# ACME_V4.net
KiCad netlist of a schematic drawn in EAGLE
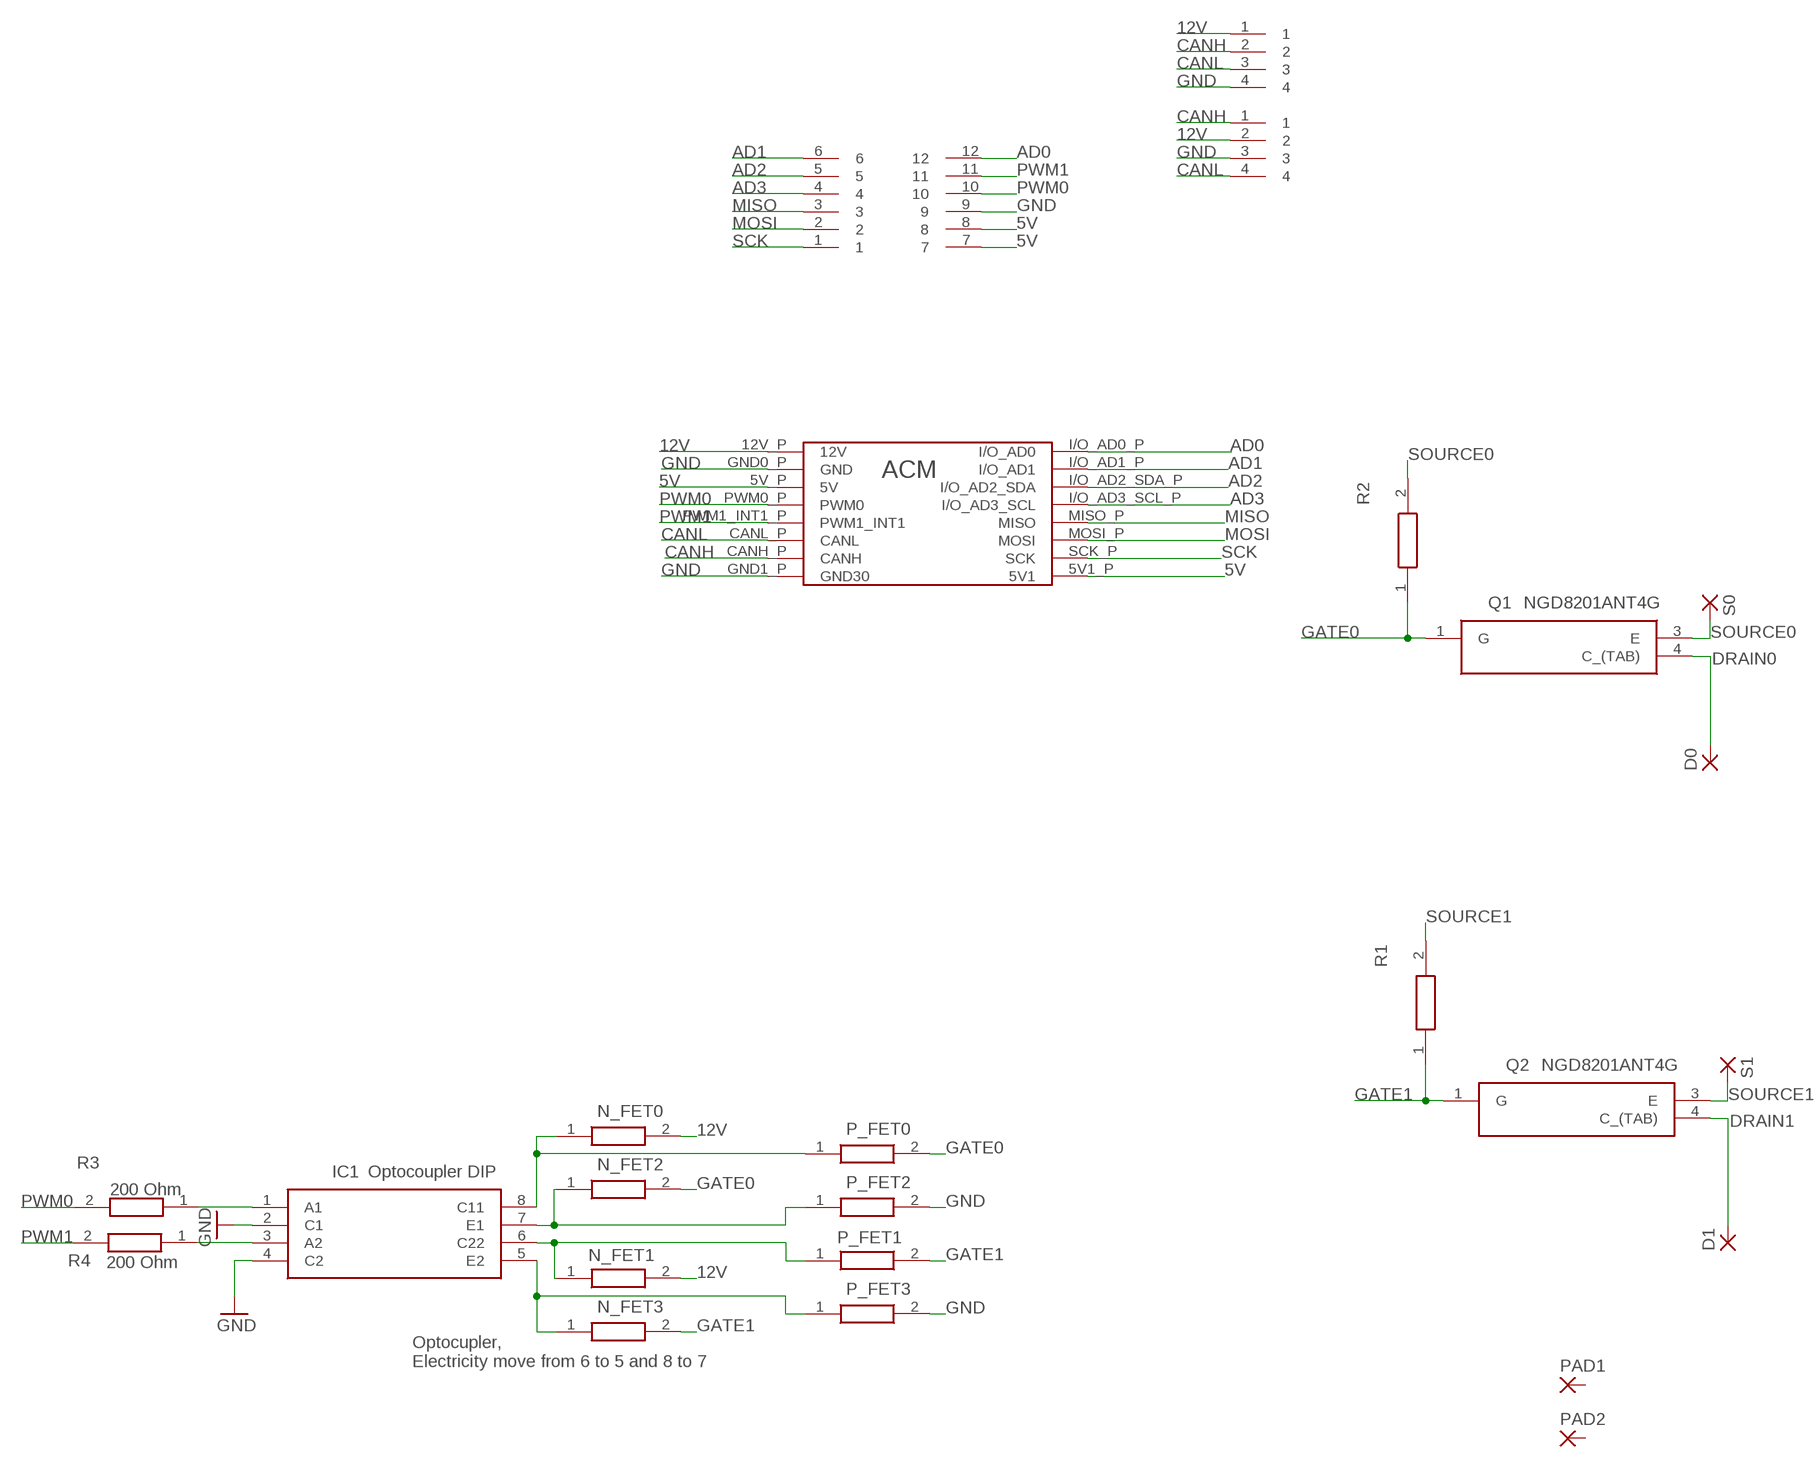
[diagram p0: schematic, sheet 1]

(export (version "E")
  (design (tool "Eeschema 10.0.6"))
  (components
    (comp (ref "D0")
      (value "WIREPADSMD5-2,5")
      (footprint "eagle-import:5-2,5")
      (libsource (lib "eagle-import") (part "WIREPADSMD5-2,5"))
    )
    (comp (ref "D1")
      (value "WIREPADSMD5-2,5")
      (footprint "eagle-import:5-2,5")
      (libsource (lib "eagle-import") (part "WIREPADSMD5-2,5"))
    )
    (comp (ref "IC1")
      (value "Optocoupler DIP")
      (footprint "eagle-import:DIP762W60P254L966H485Q8N")
      (fields
        (field (name "MANUFACTURER_PART_NUMBER") "TLP350(F)")
        (field (name "MOUSER_PART_NUMBER") "757-TLP350(F)")
        (field (name "RS_PART_NUMBER") "0186022P")
      )
      (libsource (lib "eagle-import") (part "TLP350(F)"))
    )
    (comp (ref "N_FET0")
      (value "ERA-3AEB2262V")
      (footprint "eagle-import:RESC1608X55N")
      (fields (field (name "MOUSER_PART_NUMBER") "667-ERA-3AEB2262V"))
      (libsource (lib "eagle-import") (part "ERA-3AEB2262V"))
    )
    (comp (ref "N_FET1")
      (value "ERA-3AEB2262V")
      (footprint "eagle-import:RESC1608X55N")
      (fields (field (name "MOUSER_PART_NUMBER") "667-ERA-3AEB2262V"))
      (libsource (lib "eagle-import") (part "ERA-3AEB2262V"))
    )
    (comp (ref "N_FET2")
      (value "ERA-3AEB2262V")
      (footprint "eagle-import:RESC1608X55N")
      (fields (field (name "MOUSER_PART_NUMBER") "667-ERA-3AEB2262V"))
      (libsource (lib "eagle-import") (part "ERA-3AEB2262V"))
    )
    (comp (ref "N_FET3")
      (value "ERA-3AEB2262V")
      (footprint "eagle-import:RESC1608X55N")
      (fields (field (name "MOUSER_PART_NUMBER") "667-ERA-3AEB2262V"))
      (libsource (lib "eagle-import") (part "ERA-3AEB2262V"))
    )
    (comp (ref "PAD1")
      (value "2,54/1,1")
      (footprint "eagle-import:2,54_1,1")
      (libsource (lib "eagle-import") (part "2,54/1,1"))
    )
    (comp (ref "PAD2")
      (value "2,54/1,1")
      (footprint "eagle-import:2,54_1,1")
      (libsource (lib "eagle-import") (part "2,54/1,1"))
    )
    (comp (ref "P_FET0")
      (value "ERA-3AEB2262V")
      (footprint "eagle-import:RESC1608X55N")
      (fields (field (name "MOUSER_PART_NUMBER") "667-ERA-3AEB2262V"))
      (libsource (lib "eagle-import") (part "ERA-3AEB2262V"))
    )
    (comp (ref "P_FET1")
      (value "ERA-3AEB2262V")
      (footprint "eagle-import:RESC1608X55N")
      (fields (field (name "MOUSER_PART_NUMBER") "667-ERA-3AEB2262V"))
      (libsource (lib "eagle-import") (part "ERA-3AEB2262V"))
    )
    (comp (ref "P_FET2")
      (value "ERA-3AEB2262V")
      (footprint "eagle-import:RESC1608X55N")
      (fields (field (name "MOUSER_PART_NUMBER") "667-ERA-3AEB2262V"))
      (libsource (lib "eagle-import") (part "ERA-3AEB2262V"))
    )
    (comp (ref "P_FET3")
      (value "ERA-3AEB2262V")
      (footprint "eagle-import:RESC1608X55N")
      (fields (field (name "MOUSER_PART_NUMBER") "667-ERA-3AEB2262V"))
      (libsource (lib "eagle-import") (part "ERA-3AEB2262V"))
    )
    (comp (ref "Q1")
      (value "NGD8201ANT4G")
      (footprint "eagle-import:TO229P990X238-4N")
      (fields (field (name "MOUSER_PART_NUMBER") "7470901"))
      (libsource (lib "eagle-import") (part "NGD8201ANT4G"))
    )
    (comp (ref "Q2")
      (value "NGD8201ANT4G")
      (footprint "eagle-import:TO229P990X238-4N")
      (fields (field (name "MOUSER_PART_NUMBER") "7470901"))
      (libsource (lib "eagle-import") (part "NGD8201ANT4G"))
    )
    (comp (ref "R1")
      (value "ERA-3AEB2262V")
      (footprint "eagle-import:RESC1608X55N")
      (fields (field (name "MOUSER_PART_NUMBER") "667-ERA-3AEB2262V"))
      (libsource (lib "eagle-import") (part "ERA-3AEB2262V"))
    )
    (comp (ref "R2")
      (value "ERA-3AEB2262V")
      (footprint "eagle-import:RESC1608X55N")
      (fields (field (name "MOUSER_PART_NUMBER") "667-ERA-3AEB2262V"))
      (libsource (lib "eagle-import") (part "ERA-3AEB2262V"))
    )
    (comp (ref "R3")
      (value "200 Ohm")
      (footprint "eagle-import:RESC1608X55N")
      (fields
        (field (name "MANUFACTURER_PART_NUMBER") "ERA-3AEB2262V")
        (field (name "MOUSER_PART_NUMBER") "667-ERA-3AEB2262V")
      )
      (libsource (lib "eagle-import") (part "ERA-3AEB2262V"))
    )
    (comp (ref "R4")
      (value "200 Ohm")
      (footprint "eagle-import:RESC1608X55N")
      (fields
        (field (name "MANUFACTURER_PART_NUMBER") "ERA-3AEB2262V")
        (field (name "MOUSER_PART_NUMBER") "667-ERA-3AEB2262V")
      )
      (libsource (lib "eagle-import") (part "ERA-3AEB2262V"))
    )
    (comp (ref "S0")
      (value "WIREPADSMD5-2,5")
      (footprint "eagle-import:5-2,5")
      (libsource (lib "eagle-import") (part "WIREPADSMD5-2,5"))
    )
    (comp (ref "S1")
      (value "WIREPADSMD5-2,5")
      (footprint "eagle-import:5-2,5")
      (libsource (lib "eagle-import") (part "WIREPADSMD5-2,5"))
    )
    (comp (ref "U$1")
      (value "ACM_CASTELLATED")
      (footprint "eagle-import:ACM_CAS_FP")
      (libsource (lib "eagle-import") (part "ACM_CASTELLATED"))
    )
    (comp (ref "U$2")
      (value "16P_CONNECTOR")
      (footprint "eagle-import:16P_CONNECTOR_FP")
      (libsource (lib "eagle-import") (part "16P_CONNECTOR"))
    )
    (comp (ref "U$3")
      (value "16P_CONNECTOR")
      (footprint "eagle-import:16P_CONNECTOR_FP")
      (libsource (lib "eagle-import") (part "4P_Connector holes_16P_CONNECTOR"))
    )
    (comp (ref "U$4")
      (value "16P_CONNECTOR")
      (footprint "eagle-import:16P_CONNECTOR_FP")
      (libsource (lib "eagle-import") (part "4P_Connector holes_16P_CONNECTOR"))
    )
  )
  (nets
    (net (code "1") (name "/5V") (class "Default")
      (node (ref "U$1") (pin "5V1_P") (pinfunction "5V1_5V1_P") (pintype "bidirectional"))
      (node (ref "U$1") (pin "5V_P") (pinfunction "5V_5V_P") (pintype "bidirectional"))
      (node (ref "U$2") (pin "7") (pinfunction "7_7") (pintype "bidirectional"))
      (node (ref "U$2") (pin "8") (pinfunction "8_8") (pintype "bidirectional"))
    )
    (net (code "2") (name "/12V") (class "Default")
      (node (ref "N_FET0") (pin "2") (pinfunction "2_2") (pintype "bidirectional"))
      (node (ref "N_FET1") (pin "2") (pinfunction "2_2") (pintype "bidirectional"))
      (node (ref "U$1") (pin "12V_P") (pinfunction "12V_12V_P") (pintype "bidirectional"))
      (node (ref "U$3") (pin "1") (pinfunction "1_1") (pintype "bidirectional"))
      (node (ref "U$4") (pin "2") (pinfunction "2_2") (pintype "bidirectional"))
    )
    (net (code "3") (name "/AD0") (class "Default")
      (node (ref "U$1") (pin "I/O_AD0_P") (pinfunction "I/O_AD0_I/O_AD0_P") (pintype "bidirectional"))
      (node (ref "U$2") (pin "12") (pinfunction "12_12") (pintype "bidirectional"))
    )
    (net (code "4") (name "/AD1") (class "Default")
      (node (ref "U$1") (pin "I/O_AD1_P") (pinfunction "I/O_AD1_I/O_AD1_P") (pintype "bidirectional"))
      (node (ref "U$2") (pin "6") (pinfunction "6_6") (pintype "bidirectional"))
    )
    (net (code "5") (name "/AD2") (class "Default")
      (node (ref "U$1") (pin "I/O_AD2_SDA_P") (pinfunction "I/O_AD2_SDA_I/O_AD2_SDA_P") (pintype "bidirectional"))
      (node (ref "U$2") (pin "5") (pinfunction "5_5") (pintype "bidirectional"))
    )
    (net (code "6") (name "/AD3") (class "Default")
      (node (ref "U$1") (pin "I/O_AD3_SCL_P") (pinfunction "I/O_AD3_SCL_I/O_AD3_SCL_P") (pintype "bidirectional"))
      (node (ref "U$2") (pin "4") (pinfunction "4_4") (pintype "bidirectional"))
    )
    (net (code "7") (name "/CANH") (class "Default")
      (node (ref "U$1") (pin "CANH_P") (pinfunction "CANH_CANH_P") (pintype "bidirectional"))
      (node (ref "U$3") (pin "2") (pinfunction "2_2") (pintype "bidirectional"))
      (node (ref "U$4") (pin "1") (pinfunction "1_1") (pintype "bidirectional"))
    )
    (net (code "8") (name "/CANL") (class "Default")
      (node (ref "U$1") (pin "CANL_P") (pinfunction "CANL_CANL_P") (pintype "bidirectional"))
      (node (ref "U$3") (pin "3") (pinfunction "3_3") (pintype "bidirectional"))
      (node (ref "U$4") (pin "4") (pinfunction "4_4") (pintype "bidirectional"))
    )
    (net (code "9") (name "/DRAIN0") (class "Default")
      (node (ref "D0") (pin "1") (pinfunction "P_1") (pintype "passive"))
      (node (ref "Q1") (pin "4") (pinfunction "C_(TAB)_4") (pintype "bidirectional"))
    )
    (net (code "10") (name "/DRAIN1") (class "Default")
      (node (ref "D1") (pin "1") (pinfunction "P_1") (pintype "passive"))
      (node (ref "Q2") (pin "4") (pinfunction "C_(TAB)_4") (pintype "bidirectional"))
    )
    (net (code "11") (name "/GATE0") (class "Default")
      (node (ref "N_FET2") (pin "2") (pinfunction "2_2") (pintype "bidirectional"))
      (node (ref "P_FET0") (pin "2") (pinfunction "2_2") (pintype "bidirectional"))
      (node (ref "Q1") (pin "1") (pinfunction "G_1") (pintype "bidirectional"))
      (node (ref "R2") (pin "1") (pinfunction "1_1") (pintype "bidirectional"))
    )
    (net (code "12") (name "/GATE1") (class "Default")
      (node (ref "N_FET3") (pin "2") (pinfunction "2_2") (pintype "bidirectional"))
      (node (ref "P_FET1") (pin "2") (pinfunction "2_2") (pintype "bidirectional"))
      (node (ref "Q2") (pin "1") (pinfunction "G_1") (pintype "bidirectional"))
      (node (ref "R1") (pin "1") (pinfunction "1_1") (pintype "bidirectional"))
    )
    (net (code "13") (name "/MISO") (class "Default")
      (node (ref "U$1") (pin "MISO_P") (pinfunction "MISO_MISO_P") (pintype "bidirectional"))
      (node (ref "U$2") (pin "3") (pinfunction "3_3") (pintype "bidirectional"))
    )
    (net (code "14") (name "/MOSI") (class "Default")
      (node (ref "U$1") (pin "MOSI_P") (pinfunction "MOSI_MOSI_P") (pintype "bidirectional"))
      (node (ref "U$2") (pin "2") (pinfunction "2_2") (pintype "bidirectional"))
    )
    (net (code "15") (name "/PWM0") (class "Default")
      (node (ref "R3") (pin "2") (pinfunction "2_2") (pintype "bidirectional"))
      (node (ref "U$1") (pin "PWM0_P") (pinfunction "PWM0_PWM0_P") (pintype "bidirectional"))
      (node (ref "U$2") (pin "10") (pinfunction "10_10") (pintype "bidirectional"))
    )
    (net (code "16") (name "/PWM1") (class "Default")
      (node (ref "R4") (pin "2") (pinfunction "2_2") (pintype "bidirectional"))
      (node (ref "U$1") (pin "PWM1_INT1_P") (pinfunction "PWM1_INT1_PWM1_INT1_P") (pintype "bidirectional"))
      (node (ref "U$2") (pin "11") (pinfunction "11_11") (pintype "bidirectional"))
    )
    (net (code "17") (name "/SCK") (class "Default")
      (node (ref "U$1") (pin "SCK_P") (pinfunction "SCK_SCK_P") (pintype "bidirectional"))
      (node (ref "U$2") (pin "1") (pinfunction "1_1") (pintype "bidirectional"))
    )
    (net (code "18") (name "/SOURCE0") (class "Default")
      (node (ref "Q1") (pin "3") (pinfunction "E_3") (pintype "bidirectional"))
      (node (ref "R2") (pin "2") (pinfunction "2_2") (pintype "bidirectional"))
      (node (ref "S0") (pin "1") (pinfunction "P_1") (pintype "passive"))
    )
    (net (code "19") (name "/SOURCE1") (class "Default")
      (node (ref "Q2") (pin "3") (pinfunction "E_3") (pintype "bidirectional"))
      (node (ref "R1") (pin "2") (pinfunction "2_2") (pintype "bidirectional"))
      (node (ref "S1") (pin "1") (pinfunction "P_1") (pintype "passive"))
    )
    (net (code "20") (name "GND") (class "Default")
      (node (ref "IC1") (pin "2") (pinfunction "C1_2") (pintype "bidirectional"))
      (node (ref "IC1") (pin "4") (pinfunction "C2_4") (pintype "bidirectional"))
      (node (ref "P_FET2") (pin "2") (pinfunction "2_2") (pintype "bidirectional"))
      (node (ref "P_FET3") (pin "2") (pinfunction "2_2") (pintype "bidirectional"))
      (node (ref "U$1") (pin "GND0_P") (pinfunction "GND_GND0_P") (pintype "bidirectional"))
      (node (ref "U$1") (pin "GND1_P") (pinfunction "GND30_GND1_P") (pintype "bidirectional"))
      (node (ref "U$2") (pin "9") (pinfunction "9_9") (pintype "bidirectional"))
      (node (ref "U$3") (pin "4") (pinfunction "4_4") (pintype "bidirectional"))
      (node (ref "U$4") (pin "3") (pinfunction "3_3") (pintype "bidirectional"))
    )
    (net (code "21") (name "Net-(IC1-A1)") (class "Default")
      (node (ref "IC1") (pin "1") (pinfunction "A1_1") (pintype "bidirectional"))
      (node (ref "R3") (pin "1") (pinfunction "1_1") (pintype "bidirectional"))
    )
    (net (code "22") (name "Net-(IC1-A2)") (class "Default")
      (node (ref "IC1") (pin "3") (pinfunction "A2_3") (pintype "bidirectional"))
      (node (ref "R4") (pin "1") (pinfunction "1_1") (pintype "bidirectional"))
    )
    (net (code "23") (name "Net-(IC1-C11)") (class "Default")
      (node (ref "IC1") (pin "8") (pinfunction "C11_8") (pintype "bidirectional"))
      (node (ref "N_FET0") (pin "1") (pinfunction "1_1") (pintype "bidirectional"))
      (node (ref "P_FET0") (pin "1") (pinfunction "1_1") (pintype "bidirectional"))
    )
    (net (code "24") (name "Net-(IC1-C22)") (class "Default")
      (node (ref "IC1") (pin "6") (pinfunction "C22_6") (pintype "bidirectional"))
      (node (ref "N_FET1") (pin "1") (pinfunction "1_1") (pintype "bidirectional"))
      (node (ref "P_FET1") (pin "1") (pinfunction "1_1") (pintype "bidirectional"))
    )
    (net (code "25") (name "Net-(IC1-E1)") (class "Default")
      (node (ref "IC1") (pin "7") (pinfunction "E1_7") (pintype "bidirectional"))
      (node (ref "N_FET2") (pin "1") (pinfunction "1_1") (pintype "bidirectional"))
      (node (ref "P_FET2") (pin "1") (pinfunction "1_1") (pintype "bidirectional"))
    )
    (net (code "26") (name "Net-(IC1-E2)") (class "Default")
      (node (ref "IC1") (pin "5") (pinfunction "E2_5") (pintype "bidirectional"))
      (node (ref "N_FET3") (pin "1") (pinfunction "1_1") (pintype "bidirectional"))
      (node (ref "P_FET3") (pin "1") (pinfunction "1_1") (pintype "bidirectional"))
    )
    (net (code "27") (name "unconnected-(PAD1-P-Pad1)") (class "Default")
      (node (ref "PAD1") (pin "1") (pinfunction "P_1") (pintype "passive"))
    )
    (net (code "28") (name "unconnected-(PAD2-P-Pad1)") (class "Default")
      (node (ref "PAD2") (pin "1") (pinfunction "P_1") (pintype "passive"))
    )
  )
)
